# AlarmLeuchte.net
KiCad netlist of a schematic drawn in EAGLE
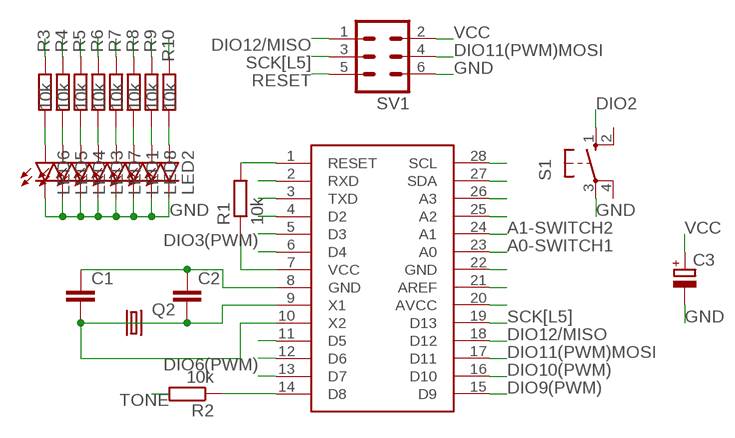
[diagram p0: schematic, sheet 1]

(export (version "E")
  (design (tool "Eeschema 10.0.6"))
  (components
    (comp (ref "C1")
      (value "C-EU025-024X044")
      (footprint "eagle-import:C025-024X044")
      (libsource (lib "eagle-import") (part "C-EU025-024X044"))
    )
    (comp (ref "C2")
      (value "C-EU025-024X044")
      (footprint "eagle-import:C025-024X044")
      (libsource (lib "eagle-import") (part "C-EU025-024X044"))
    )
    (comp (ref "C3")
      (value "CPOL-EUE3.5-8")
      (footprint "eagle-import:E3,5-8")
      (libsource (lib "eagle-import") (part "CPOL-EUE3.5-8"))
    )
    (comp (ref "LED1")
      (value "LED5MM")
      (footprint "eagle-import:LED5MM")
      (libsource (lib "eagle-import") (part "LED5MM"))
    )
    (comp (ref "LED2")
      (value "LED5MM")
      (footprint "eagle-import:LED5MM")
      (libsource (lib "eagle-import") (part "LED5MM"))
    )
    (comp (ref "LED3")
      (value "LED5MM")
      (footprint "eagle-import:LED5MM")
      (libsource (lib "eagle-import") (part "LED5MM"))
    )
    (comp (ref "LED4")
      (value "LED5MM")
      (footprint "eagle-import:LED5MM")
      (libsource (lib "eagle-import") (part "LED5MM"))
    )
    (comp (ref "LED5")
      (value "LED5MM")
      (footprint "eagle-import:LED5MM")
      (libsource (lib "eagle-import") (part "LED5MM"))
    )
    (comp (ref "LED6")
      (value "LED5MM")
      (footprint "eagle-import:LED5MM")
      (libsource (lib "eagle-import") (part "LED5MM"))
    )
    (comp (ref "LED7")
      (value "LED5MM")
      (footprint "eagle-import:LED5MM")
      (libsource (lib "eagle-import") (part "LED5MM"))
    )
    (comp (ref "LED8")
      (value "LED5MM")
      (footprint "eagle-import:LED5MM")
      (libsource (lib "eagle-import") (part "LED5MM"))
    )
    (comp (ref "Q2")
      (value "CRYSTALHC49S")
      (footprint "eagle-import:HC49_S")
      (libsource (lib "eagle-import") (part "CRYSTALHC49S"))
    )
    (comp (ref "R1")
      (value "10k")
      (footprint "eagle-import:0207_15")
      (libsource (lib "eagle-import") (part "R-EU_0207/15"))
    )
    (comp (ref "R2")
      (value "10k")
      (footprint "eagle-import:0207_10")
      (libsource (lib "eagle-import") (part "R-EU_0207/10"))
    )
    (comp (ref "R3")
      (value "10k")
      (footprint "eagle-import:0207_10")
      (libsource (lib "eagle-import") (part "R-EU_0207/10"))
    )
    (comp (ref "R4")
      (value "10k")
      (footprint "eagle-import:0207_10")
      (libsource (lib "eagle-import") (part "R-EU_0207/10"))
    )
    (comp (ref "R5")
      (value "10k")
      (footprint "eagle-import:0207_10")
      (libsource (lib "eagle-import") (part "R-EU_0207/10"))
    )
    (comp (ref "R6")
      (value "10k")
      (footprint "eagle-import:0207_10")
      (libsource (lib "eagle-import") (part "R-EU_0207/10"))
    )
    (comp (ref "R7")
      (value "10k")
      (footprint "eagle-import:0207_10")
      (libsource (lib "eagle-import") (part "R-EU_0207/10"))
    )
    (comp (ref "R8")
      (value "10k")
      (footprint "eagle-import:0207_10")
      (libsource (lib "eagle-import") (part "R-EU_0207/10"))
    )
    (comp (ref "R9")
      (value "10k")
      (footprint "eagle-import:0207_10")
      (libsource (lib "eagle-import") (part "R-EU_0207/10"))
    )
    (comp (ref "R10")
      (value "10k")
      (footprint "eagle-import:0204_7")
      (libsource (lib "eagle-import") (part "R-EU_0204/7"))
    )
    (comp (ref "S1")
      (value "10-XX")
      (footprint "eagle-import:B3F-10XX")
      (fields (field (name "MPN") "B3F-1000"))
      (libsource (lib "eagle-import") (part "10-XX"))
    )
    (comp (ref "SV1")
      (value "MA03-2")
      (footprint "eagle-import:MA03-2")
      (libsource (lib "eagle-import") (part "MA03-2"))
    )
    (comp (ref "U$1")
      (value "ATMEGA328P-PU")
      (footprint "eagle-import:DIL28-3")
      (libsource (lib "eagle-import") (part "ATMEGA328P-PU"))
    )
  )
  (nets
    (net (code "1") (name "/A0-SWITCH1") (class "Default")
      (node (ref "U$1") (pin "23") (pinfunction "A0_23") (pintype "bidirectional"))
    )
    (net (code "2") (name "/A1-SWITCH2") (class "Default")
      (node (ref "U$1") (pin "24") (pinfunction "A1_24") (pintype "bidirectional"))
    )
    (net (code "3") (name "/A5[SCL]") (class "Default")
      (node (ref "R9") (pin "1") (pinfunction "1_1") (pintype "passive"))
      (node (ref "U$1") (pin "28") (pinfunction "SCL_28") (pintype "bidirectional"))
    )
    (net (code "4") (name "/DIO2") (class "Default")
      (node (ref "S1") (pin "1") (pinfunction "S_1") (pintype "passive"))
      (node (ref "U$1") (pin "25") (pinfunction "A2_25") (pintype "bidirectional"))
      (node (ref "U$1") (pin "4") (pinfunction "D2_4") (pintype "bidirectional"))
    )
    (net (code "5") (name "/DIO3(PWM)") (class "Default")
      (node (ref "R8") (pin "1") (pinfunction "1_1") (pintype "passive"))
      (node (ref "U$1") (pin "5") (pinfunction "D3_5") (pintype "bidirectional"))
    )
    (net (code "6") (name "/DIO4") (class "Default")
      (node (ref "R7") (pin "1") (pinfunction "1_1") (pintype "passive"))
      (node (ref "U$1") (pin "6") (pinfunction "D4_6") (pintype "bidirectional"))
    )
    (net (code "7") (name "/DIO5(PWM)") (class "Default")
      (node (ref "R5") (pin "1") (pinfunction "1_1") (pintype "passive"))
      (node (ref "U$1") (pin "11") (pinfunction "D5_11") (pintype "bidirectional"))
    )
    (net (code "8") (name "/DIO6(PWM)") (class "Default")
      (node (ref "R10") (pin "1") (pinfunction "1_1") (pintype "passive"))
      (node (ref "U$1") (pin "12") (pinfunction "D6_12") (pintype "bidirectional"))
    )
    (net (code "9") (name "/DIO7") (class "Default")
      (node (ref "R3") (pin "1") (pinfunction "1_1") (pintype "passive"))
      (node (ref "U$1") (pin "13") (pinfunction "D7_13") (pintype "bidirectional"))
    )
    (net (code "10") (name "/DIO9(PWM)") (class "Default")
      (node (ref "R4") (pin "1") (pinfunction "1_1") (pintype "passive"))
      (node (ref "U$1") (pin "15") (pinfunction "D9_15") (pintype "bidirectional"))
    )
    (net (code "11") (name "/DIO10(PWM)") (class "Default")
      (node (ref "R6") (pin "1") (pinfunction "1_1") (pintype "passive"))
      (node (ref "U$1") (pin "16") (pinfunction "D10_16") (pintype "bidirectional"))
    )
    (net (code "12") (name "/DIO11(PWM)MOSI") (class "Default")
      (node (ref "SV1") (pin "4") (pinfunction "4_4") (pintype "passive"))
      (node (ref "U$1") (pin "17") (pinfunction "D11_17") (pintype "bidirectional"))
    )
    (net (code "13") (name "/DIO12{slash}MISO") (class "Default")
      (node (ref "SV1") (pin "1") (pinfunction "1_1") (pintype "passive"))
      (node (ref "U$1") (pin "18") (pinfunction "D12_18") (pintype "bidirectional"))
    )
    (net (code "14") (name "/GND") (class "Default")
      (node (ref "C1") (pin "1") (pinfunction "1_1") (pintype "passive"))
      (node (ref "C2") (pin "1") (pinfunction "1_1") (pintype "passive"))
      (node (ref "C3") (pin "-") (pinfunction "-_-") (pintype "passive"))
      (node (ref "LED1") (pin "K") (pinfunction "C_K") (pintype "passive"))
      (node (ref "LED2") (pin "K") (pinfunction "C_K") (pintype "passive"))
      (node (ref "LED3") (pin "K") (pinfunction "C_K") (pintype "passive"))
      (node (ref "LED4") (pin "K") (pinfunction "C_K") (pintype "passive"))
      (node (ref "LED5") (pin "K") (pinfunction "C_K") (pintype "passive"))
      (node (ref "LED6") (pin "K") (pinfunction "C_K") (pintype "passive"))
      (node (ref "LED7") (pin "K") (pinfunction "C_K") (pintype "passive"))
      (node (ref "LED8") (pin "K") (pinfunction "C_K") (pintype "passive"))
      (node (ref "S1") (pin "3") (pinfunction "P_3") (pintype "passive"))
      (node (ref "SV1") (pin "6") (pinfunction "6_6") (pintype "passive"))
      (node (ref "U$1") (pin "22") (pinfunction "GND_22") (pintype "bidirectional"))
      (node (ref "U$1") (pin "8") (pinfunction "GND_8") (pintype "bidirectional"))
    )
    (net (code "15") (name "/RESET") (class "Default")
      (node (ref "R1") (pin "2") (pinfunction "2_2") (pintype "passive"))
      (node (ref "SV1") (pin "5") (pinfunction "5_5") (pintype "passive"))
      (node (ref "U$1") (pin "1") (pinfunction "RESET_1") (pintype "bidirectional"))
    )
    (net (code "16") (name "/SCK[L5]") (class "Default")
      (node (ref "SV1") (pin "3") (pinfunction "3_3") (pintype "passive"))
      (node (ref "U$1") (pin "19") (pinfunction "D13_19") (pintype "bidirectional"))
    )
    (net (code "17") (name "/TONE") (class "Default")
      (node (ref "R2") (pin "2") (pinfunction "2_2") (pintype "passive"))
    )
    (net (code "18") (name "/VCC") (class "Default")
      (node (ref "C3") (pin "+") (pinfunction "+_+") (pintype "passive"))
      (node (ref "R1") (pin "1") (pinfunction "1_1") (pintype "passive"))
      (node (ref "SV1") (pin "2") (pinfunction "2_2") (pintype "passive"))
      (node (ref "U$1") (pin "20") (pinfunction "AVCC_20") (pintype "bidirectional"))
      (node (ref "U$1") (pin "7") (pinfunction "VCC_7") (pintype "bidirectional"))
    )
    (net (code "19") (name "Net-(LED1-PadA)") (class "Default")
      (node (ref "LED1") (pin "A") (pinfunction "A_A") (pintype "passive"))
      (node (ref "R8") (pin "2") (pinfunction "2_2") (pintype "passive"))
    )
    (net (code "20") (name "Net-(LED2-PadA)") (class "Default")
      (node (ref "LED2") (pin "A") (pinfunction "A_A") (pintype "passive"))
      (node (ref "R10") (pin "2") (pinfunction "2_2") (pintype "passive"))
    )
    (net (code "21") (name "Net-(LED3-PadA)") (class "Default")
      (node (ref "LED3") (pin "A") (pinfunction "A_A") (pintype "passive"))
      (node (ref "R6") (pin "2") (pinfunction "2_2") (pintype "passive"))
    )
    (net (code "22") (name "Net-(LED4-PadA)") (class "Default")
      (node (ref "LED4") (pin "A") (pinfunction "A_A") (pintype "passive"))
      (node (ref "R5") (pin "2") (pinfunction "2_2") (pintype "passive"))
    )
    (net (code "23") (name "Net-(LED5-PadA)") (class "Default")
      (node (ref "LED5") (pin "A") (pinfunction "A_A") (pintype "passive"))
      (node (ref "R4") (pin "2") (pinfunction "2_2") (pintype "passive"))
    )
    (net (code "24") (name "Net-(LED6-PadA)") (class "Default")
      (node (ref "LED6") (pin "A") (pinfunction "A_A") (pintype "passive"))
      (node (ref "R3") (pin "2") (pinfunction "2_2") (pintype "passive"))
    )
    (net (code "25") (name "Net-(LED7-PadA)") (class "Default")
      (node (ref "LED7") (pin "A") (pinfunction "A_A") (pintype "passive"))
      (node (ref "R7") (pin "2") (pinfunction "2_2") (pintype "passive"))
    )
    (net (code "26") (name "Net-(LED8-PadA)") (class "Default")
      (node (ref "LED8") (pin "A") (pinfunction "A_A") (pintype "passive"))
      (node (ref "R9") (pin "2") (pinfunction "2_2") (pintype "passive"))
    )
    (net (code "27") (name "Net-(U$1-D8)") (class "Default")
      (node (ref "R2") (pin "1") (pinfunction "1_1") (pintype "passive"))
      (node (ref "U$1") (pin "14") (pinfunction "D8_14") (pintype "bidirectional"))
    )
    (net (code "28") (name "Net-(U$1-X1)") (class "Default")
      (node (ref "C2") (pin "2") (pinfunction "2_2") (pintype "passive"))
      (node (ref "Q2") (pin "1") (pinfunction "1_1") (pintype "passive"))
      (node (ref "U$1") (pin "9") (pinfunction "X1_9") (pintype "bidirectional"))
    )
    (net (code "29") (name "Net-(U$1-X2)") (class "Default")
      (node (ref "C1") (pin "2") (pinfunction "2_2") (pintype "passive"))
      (node (ref "Q2") (pin "2") (pinfunction "2_2") (pintype "passive"))
      (node (ref "U$1") (pin "10") (pinfunction "X2_10") (pintype "bidirectional"))
    )
    (net (code "30") (name "unconnected-(S1-P1-Pad4)") (class "Default")
      (node (ref "S1") (pin "4") (pinfunction "P1_4") (pintype "passive"))
    )
    (net (code "31") (name "unconnected-(S1-S1-Pad2)") (class "Default")
      (node (ref "S1") (pin "2") (pinfunction "S1_2") (pintype "passive"))
    )
    (net (code "32") (name "unconnected-(U$1-A3-Pad26)") (class "Default")
      (node (ref "U$1") (pin "26") (pinfunction "A3_26") (pintype "bidirectional"))
    )
    (net (code "33") (name "unconnected-(U$1-AREF-Pad21)") (class "Default")
      (node (ref "U$1") (pin "21") (pinfunction "AREF_21") (pintype "bidirectional"))
    )
    (net (code "34") (name "unconnected-(U$1-RXD-Pad2)") (class "Default")
      (node (ref "U$1") (pin "2") (pinfunction "RXD_2") (pintype "bidirectional"))
    )
    (net (code "35") (name "unconnected-(U$1-SDA-Pad27)") (class "Default")
      (node (ref "U$1") (pin "27") (pinfunction "SDA_27") (pintype "bidirectional"))
    )
    (net (code "36") (name "unconnected-(U$1-TXD-Pad3)") (class "Default")
      (node (ref "U$1") (pin "3") (pinfunction "TXD_3") (pintype "bidirectional"))
    )
  )
)
